# externalConnectors.net
KiCad netlist of a schematic drawn in Altium Designer
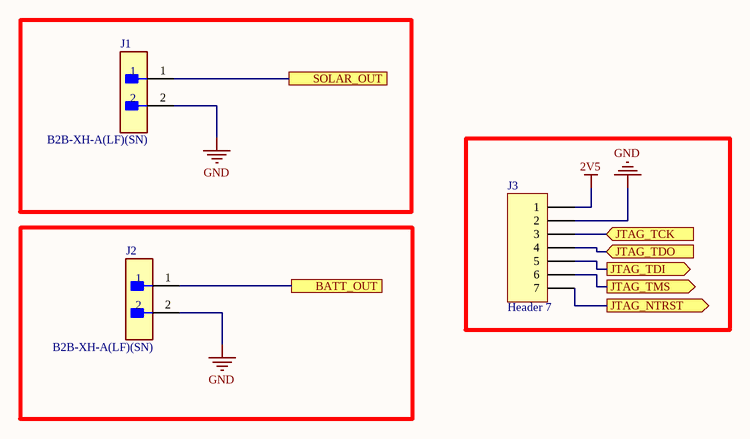
[diagram p0: externalConnectors.SchDoc]

(export (version "E")
  (design (tool "Eeschema 10.0.6"))
  (components
    (comp (ref "J1")
      (value "B2B-XH-A(LF)(SN)")
      (footprint "FP-B2B-XH-A_LF_SN-MFG")
      (description "CONN HEADER VERT 2POS 2.5MM")
      (libsource (lib "JST_Hembra_2pin") (part "CMP-2000-05888-3"))
    )
    (comp (ref "J2")
      (value "B2B-XH-A(LF)(SN)")
      (footprint "FP-B2B-XH-A_LF_SN-MFG")
      (description "CONN HEADER VERT 2POS 2.5MM")
      (libsource (lib "JST_Hembra_2pin") (part "CMP-2000-05888-3"))
    )
    (comp (ref "J3")
      (value "Header 7")
      (footprint "HDR1X7")
      (description "Header, 7-Pin")
      (fields (field (name "PUBLISHER") "Altium Limited"))
      (libsource (lib "Miscellaneous Connectors") (part "Header 7"))
    )
  )
  (nets
    (net (code "1") (name "/BATT_OUT") (class "Default")
      (node (ref "J2") (pin "1") (pinfunction "1_1") (pintype "passive"))
    )
    (net (code "2") (name "/JTAG_NTRST") (class "Default")
      (node (ref "J3") (pin "7") (pinfunction "7_7") (pintype "passive"))
    )
    (net (code "3") (name "/JTAG_TCK") (class "Default")
      (node (ref "J3") (pin "3") (pinfunction "3_3") (pintype "passive"))
    )
    (net (code "4") (name "/JTAG_TDI") (class "Default")
      (node (ref "J3") (pin "5") (pinfunction "5_5") (pintype "passive"))
    )
    (net (code "5") (name "/JTAG_TDO") (class "Default")
      (node (ref "J3") (pin "4") (pinfunction "4_4") (pintype "passive"))
    )
    (net (code "6") (name "/JTAG_TMS") (class "Default")
      (node (ref "J3") (pin "6") (pinfunction "6_6") (pintype "passive"))
    )
    (net (code "7") (name "/SOLAR_OUT") (class "Default")
      (node (ref "J1") (pin "1") (pinfunction "1_1") (pintype "passive"))
    )
    (net (code "8") (name "2V5") (class "Default")
      (node (ref "J3") (pin "1") (pinfunction "1_1") (pintype "passive"))
    )
    (net (code "9") (name "GND") (class "Default")
      (node (ref "J1") (pin "2") (pinfunction "2_2") (pintype "passive"))
      (node (ref "J2") (pin "2") (pinfunction "2_2") (pintype "passive"))
      (node (ref "J3") (pin "2") (pinfunction "2_2") (pintype "passive"))
    )
  )
)
